# CAN_Interface.net
KiCad netlist of a schematic drawn in Altium Designer
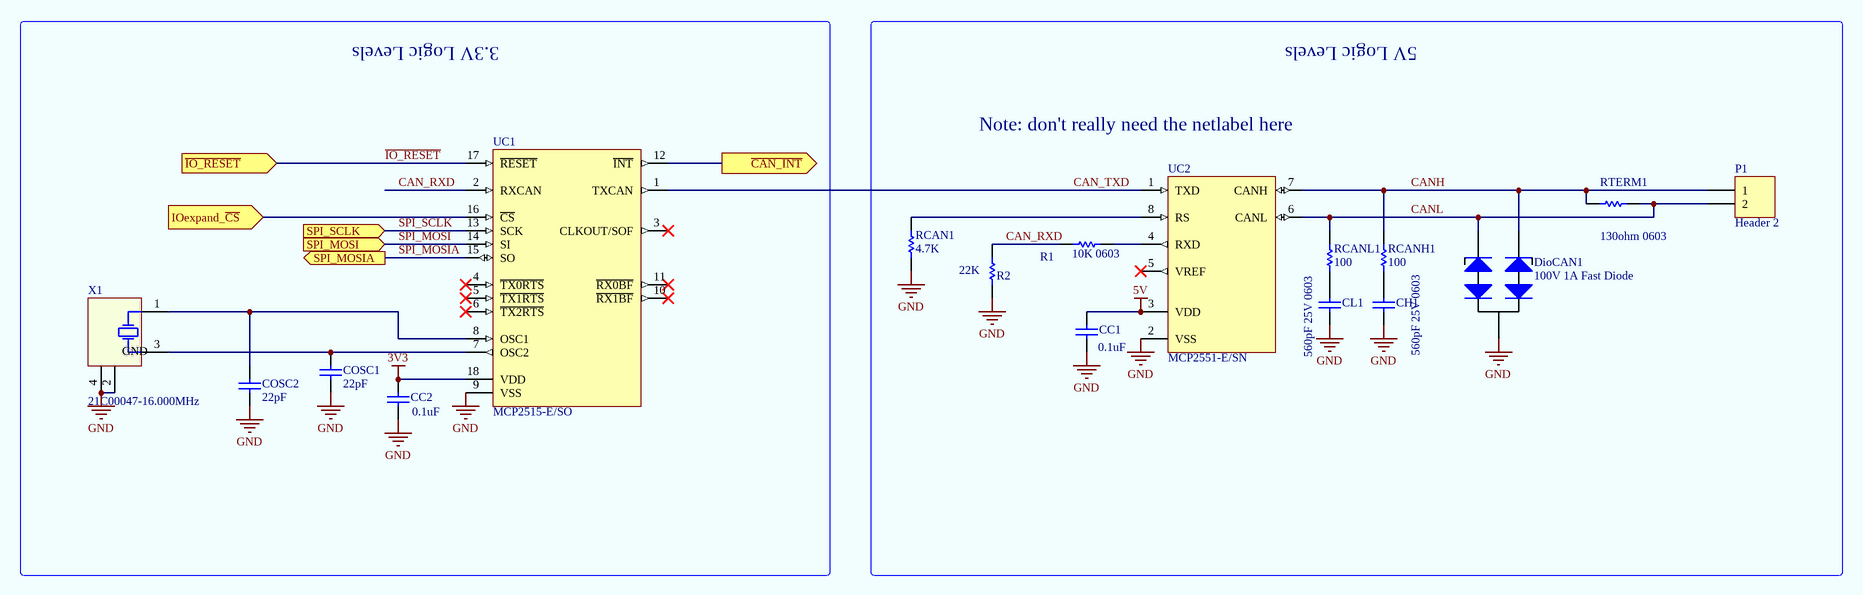
[diagram p0: CAN_Interface.SchDoc]

(export (version "E")
  (design (tool "Eeschema 10.0.6"))
  (components
    (comp (ref "CC1")
      (value "0.1uF")
      (footprint "0603C_L")
      (libsource (lib "ICEdigikey") (part "Cap10uF_25V_0603"))
    )
    (comp (ref "CC2")
      (value "0.1uF")
      (footprint "0603C_L")
      (libsource (lib "ICEdigikey") (part "Cap10uF_25V_0603"))
    )
    (comp (ref "CH1")
      (value "560pF 25V 0603")
      (footprint "0603C_L")
      (fields
        (field (name "MANUFACTURER") "Taiyo Yuden")
        (field (name "MANUFACTURER PART NUMBER") "TMK316F106ZL-T")
        (field (name "TOLERANCE") "-20%, +80%")
      )
      (libsource (lib "ICEdigikey") (part "Cap10uF_25V_0603"))
    )
    (comp (ref "CL1")
      (value "560pF 25V 0603")
      (footprint "0603C_L")
      (fields
        (field (name "MANUFACTURER") "Taiyo Yuden")
        (field (name "MANUFACTURER PART NUMBER") "TMK316F106ZL-T")
        (field (name "TOLERANCE") "-20%, +80%")
      )
      (libsource (lib "ICEdigikey") (part "Cap10uF_25V_0603"))
    )
    (comp (ref "COSC1")
      (value "22pF")
      (footprint "0603C_L")
      (fields
        (field (name "MANUFACTURER") "Murata")
        (field (name "MANUFACTURER PART NUMBER") "GRM1885C1H220JA01D")
        (field (name "TOLERANCE") "5")
      )
      (libsource (lib "PoleV2PaintV5") (part "Cap101nF_50V_0603"))
    )
    (comp (ref "COSC2")
      (value "22pF")
      (footprint "0603C_L")
      (fields
        (field (name "MANUFACTURER") "Murata")
        (field (name "MANUFACTURER PART NUMBER") "GRM1885C1H220JA01D")
        (field (name "TOLERANCE") "5")
      )
      (libsource (lib "PoleV2PaintV5") (part "Cap101nF_50V_0603"))
    )
    (comp (ref "DioCAN1")
      (value "100V 1A Fast Diode")
      (footprint "SOT23")
      (description "High Conductance Fast Diode")
      (fields
        (field (name "MANUFACTURER") "ON Semiconductor")
        (field (name "MANUFACTURER PART NUMBER") "MUR110RLG")
      )
      (libsource (lib "PoleV2PaintV5") (part "PESD1CAN"))
    )
    (comp (ref "P1")
      (value "Header 2")
      (footprint "HDR1X2")
      (description "Header, 2-Pin")
      (fields (field (name "PUBLISHER") "Altium Limited"))
      (libsource (lib "Miscellaneous Connectors") (part "Header 2"))
    )
    (comp (ref "R1")
      (value "10K 0603")
      (footprint "0603_L")
      (fields
        (field (name "MANUFACTURER") "Yageo")
        (field (name "MANUFACTURER PART NUMBER") "RT0603DRD074K99L")
        (field (name "TOLERANCE") "±0.5%")
      )
      (libsource (lib "ICEdigikey") (part "Res4K99_0603"))
    )
    (comp (ref "R2")
      (value "22K")
      (footprint "0603_L")
      (fields
        (field (name "MANUFACTURER") "Yageo")
        (field (name "MANUFACTURER PART NUMBER") "RT0603DRD0722KL")
        (field (name "TOLERANCE") "0.5 %")
      )
      (libsource (lib "ICEdigikey") (part "Res_0603"))
    )
    (comp (ref "RCAN1")
      (value "4.7K")
      (footprint "0603_L")
      (fields
        (field (name "MANUFACTURER") "Yageo")
        (field (name "MANUFACTURER PART NUMBER") "RT0603DRD074K99L")
        (field (name "TOLERANCE") "±0.5%")
      )
      (libsource (lib "ICEdigikey") (part "Res4K99_0603"))
    )
    (comp (ref "RCANH1")
      (value "100")
      (footprint "0603_L")
      (fields
        (field (name "MANUFACTURER") "Yageo")
        (field (name "MANUFACTURER PART NUMBER") "RC0603JR-07330RL")
        (field (name "TOLERANCE") "±5%")
      )
      (libsource (lib "ICEdigikey") (part "Res330_0603"))
    )
    (comp (ref "RCANL1")
      (value "100")
      (footprint "0603_L")
      (fields
        (field (name "MANUFACTURER") "Yageo")
        (field (name "MANUFACTURER PART NUMBER") "RC0603JR-07330RL")
        (field (name "TOLERANCE") "±5%")
      )
      (libsource (lib "ICEdigikey") (part "Res330_0603"))
    )
    (comp (ref "RTERM1")
      (value "130ohm 0603")
      (footprint "0603_L")
      (libsource (lib "ICEdigikey") (part "Res330_0603"))
    )
    (comp (ref "UC1")
      (value "MCP2515-E/SO")
      (footprint "SOIC-SO18_M")
      (description "Stand-Alone CAN Controller With SPI Interface, 18-Pin SOIC, Extended Temperature")
      (libsource (lib "Altium Content Vault") (part "CMP-0186-00035-2"))
    )
    (comp (ref "UC2")
      (value "MCP2551-E/SN")
      (footprint "SOIC-SN8_N")
      (description "High-Speed CAN Transceiver, 8-Pin SOIC, Extended Temperature")
      (libsource (lib "Altium Content Vault") (part "CMP-0186-00038-2"))
    )
    (comp (ref "X1")
      (value "21C00047-16.000MHz")
      (footprint "ITTI-21C00047-16.000MHz-4_V")
      (description "Crystal, 16 MHz, -30 to 85 degC, 3.2 x 2.5 x 0.9 mm SMD")
      (fields (field (name "MANUFACTURER") "ITTI"))
      (libsource (lib "Altium Content Vault") (part "CMP-0464-00001-2"))
    )
  )
  (nets
    (net (code "1") (name "/CANH") (class "Default")
      (node (ref "DioCAN1") (pin "1") (pinfunction "A_1") (pintype "passive"))
      (node (ref "P1") (pin "1") (pinfunction "1_1") (pintype "passive"))
      (node (ref "RCANH1") (pin "2") (pinfunction "2_2") (pintype "passive"))
      (node (ref "RTERM1") (pin "2") (pinfunction "2_2") (pintype "passive"))
      (node (ref "UC2") (pin "7") (pinfunction "CANH_7") (pintype "bidirectional"))
    )
    (net (code "2") (name "/CANL") (class "Default")
      (node (ref "DioCAN1") (pin "2") (pinfunction "K_2") (pintype "passive"))
      (node (ref "P1") (pin "2") (pinfunction "2_2") (pintype "passive"))
      (node (ref "RCANL1") (pin "2") (pinfunction "2_2") (pintype "passive"))
      (node (ref "RTERM1") (pin "1") (pinfunction "1_1") (pintype "passive"))
      (node (ref "UC2") (pin "6") (pinfunction "CANL_6") (pintype "bidirectional"))
    )
    (net (code "3") (name "/CAN_INT") (class "Default")
      (node (ref "UC1") (pin "12") (pinfunction "~{INT}_12") (pintype "output"))
    )
    (net (code "4") (name "/CAN_RXD") (class "Default")
      (node (ref "R1") (pin "2") (pinfunction "2_2") (pintype "passive"))
      (node (ref "R2") (pin "2") (pinfunction "2_2") (pintype "passive"))
      (node (ref "UC1") (pin "2") (pinfunction "RXCAN_2") (pintype "input"))
    )
    (net (code "5") (name "/CAN_TXD") (class "Default")
      (node (ref "UC1") (pin "1") (pinfunction "TXCAN_1") (pintype "output"))
      (node (ref "UC2") (pin "1") (pinfunction "TXD_1") (pintype "input"))
    )
    (net (code "6") (name "/IO_RESET") (class "Default")
      (node (ref "UC1") (pin "17") (pinfunction "~{RESET}_17") (pintype "input"))
    )
    (net (code "7") (name "/IOexpand_~{CS}") (class "Default")
      (node (ref "UC1") (pin "16") (pinfunction "~{CS}_16") (pintype "input"))
    )
    (net (code "8") (name "/SPI_MOSI") (class "Default")
      (node (ref "UC1") (pin "14") (pinfunction "SI_14") (pintype "input"))
    )
    (net (code "9") (name "/SPI_MOSIA") (class "Default")
      (node (ref "UC1") (pin "15") (pinfunction "SO_15") (pintype "bidirectional"))
    )
    (net (code "10") (name "/SPI_SCLK") (class "Default")
      (node (ref "UC1") (pin "13") (pinfunction "SCK_13") (pintype "input"))
    )
    (net (code "11") (name "3V3") (class "Default")
      (node (ref "CC2") (pin "2") (pinfunction "2_2") (pintype "passive"))
      (node (ref "UC1") (pin "18") (pinfunction "VDD_18") (pintype "power_in"))
    )
    (net (code "12") (name "5V") (class "Default")
      (node (ref "CC1") (pin "2") (pinfunction "2_2") (pintype "passive"))
      (node (ref "UC2") (pin "3") (pinfunction "VDD_3") (pintype "power_in"))
    )
    (net (code "13") (name "GND") (class "Default")
      (node (ref "CC1") (pin "1") (pinfunction "1_1") (pintype "passive"))
      (node (ref "CC2") (pin "1") (pinfunction "1_1") (pintype "passive"))
      (node (ref "CH1") (pin "2") (pinfunction "2_2") (pintype "passive"))
      (node (ref "CL1") (pin "1") (pinfunction "1_1") (pintype "passive"))
      (node (ref "COSC1") (pin "1") (pinfunction "1_1") (pintype "passive"))
      (node (ref "COSC2") (pin "2") (pinfunction "2_2") (pintype "passive"))
      (node (ref "DioCAN1") (pin "3") (pinfunction "3_3") (pintype "passive"))
      (node (ref "R2") (pin "1") (pinfunction "1_1") (pintype "passive"))
      (node (ref "RCAN1") (pin "1") (pinfunction "1_1") (pintype "passive"))
      (node (ref "UC1") (pin "9") (pinfunction "VSS_9") (pintype "power_in"))
      (node (ref "UC2") (pin "2") (pinfunction "VSS_2") (pintype "power_in"))
      (node (ref "X1") (pin "2") (pinfunction "GND_2") (pintype "power_in"))
      (node (ref "X1") (pin "4") (pinfunction "GND_4") (pintype "power_in"))
    )
    (net (code "14") (name "Net-(CH1-Pad1)") (class "Default")
      (node (ref "CH1") (pin "1") (pinfunction "1_1") (pintype "passive"))
      (node (ref "RCANH1") (pin "1") (pinfunction "1_1") (pintype "passive"))
    )
    (net (code "15") (name "Net-(CL1-Pad2)") (class "Default")
      (node (ref "CL1") (pin "2") (pinfunction "2_2") (pintype "passive"))
      (node (ref "RCANL1") (pin "1") (pinfunction "1_1") (pintype "passive"))
    )
    (net (code "16") (name "Net-(UC1-OSC1)") (class "Default")
      (node (ref "COSC2") (pin "1") (pinfunction "1_1") (pintype "passive"))
      (node (ref "UC1") (pin "8") (pinfunction "OSC1_8") (pintype "input"))
      (node (ref "X1") (pin "1") (pinfunction "XTAL_1") (pintype "passive"))
    )
    (net (code "17") (name "Net-(UC1-OSC2)") (class "Default")
      (node (ref "COSC1") (pin "2") (pinfunction "2_2") (pintype "passive"))
      (node (ref "UC1") (pin "7") (pinfunction "OSC2_7") (pintype "output"))
      (node (ref "X1") (pin "3") (pinfunction "XTAL_3") (pintype "passive"))
    )
    (net (code "18") (name "Net-(UC2-RS)") (class "Default")
      (node (ref "RCAN1") (pin "2") (pinfunction "2_2") (pintype "passive"))
      (node (ref "UC2") (pin "8") (pinfunction "RS_8") (pintype "input"))
    )
    (net (code "19") (name "Net-(UC2-RXD)") (class "Default")
      (node (ref "R1") (pin "1") (pinfunction "1_1") (pintype "passive"))
      (node (ref "UC2") (pin "4") (pinfunction "RXD_4") (pintype "output"))
    )
    (net (code "20") (name "unconnected-(UC1-CLKOUT{slash}SOF-Pad3)") (class "Default")
      (node (ref "UC1") (pin "3") (pinfunction "CLKOUT/SOF_3") (pintype "output+no_connect"))
    )
    (net (code "21") (name "unconnected-(UC1-~{RX0BF}-Pad11)") (class "Default")
      (node (ref "UC1") (pin "11") (pinfunction "~{RX0BF}_11") (pintype "output+no_connect"))
    )
    (net (code "22") (name "unconnected-(UC1-~{RX1BF}-Pad10)") (class "Default")
      (node (ref "UC1") (pin "10") (pinfunction "~{RX1BF}_10") (pintype "output+no_connect"))
    )
    (net (code "23") (name "unconnected-(UC1-~{TX0RTS}-Pad4)") (class "Default")
      (node (ref "UC1") (pin "4") (pinfunction "~{TX0RTS}_4") (pintype "input+no_connect"))
    )
    (net (code "24") (name "unconnected-(UC1-~{TX1RTS}-Pad5)") (class "Default")
      (node (ref "UC1") (pin "5") (pinfunction "~{TX1RTS}_5") (pintype "input+no_connect"))
    )
    (net (code "25") (name "unconnected-(UC1-~{TX2RTS}-Pad6)") (class "Default")
      (node (ref "UC1") (pin "6") (pinfunction "~{TX2RTS}_6") (pintype "input+no_connect"))
    )
    (net (code "26") (name "unconnected-(UC2-VREF-Pad5)") (class "Default")
      (node (ref "UC2") (pin "5") (pinfunction "VREF_5") (pintype "output+no_connect"))
    )
  )
)
